# microcontroller_sch.net
KiCad netlist of a schematic drawn in Altium Designer
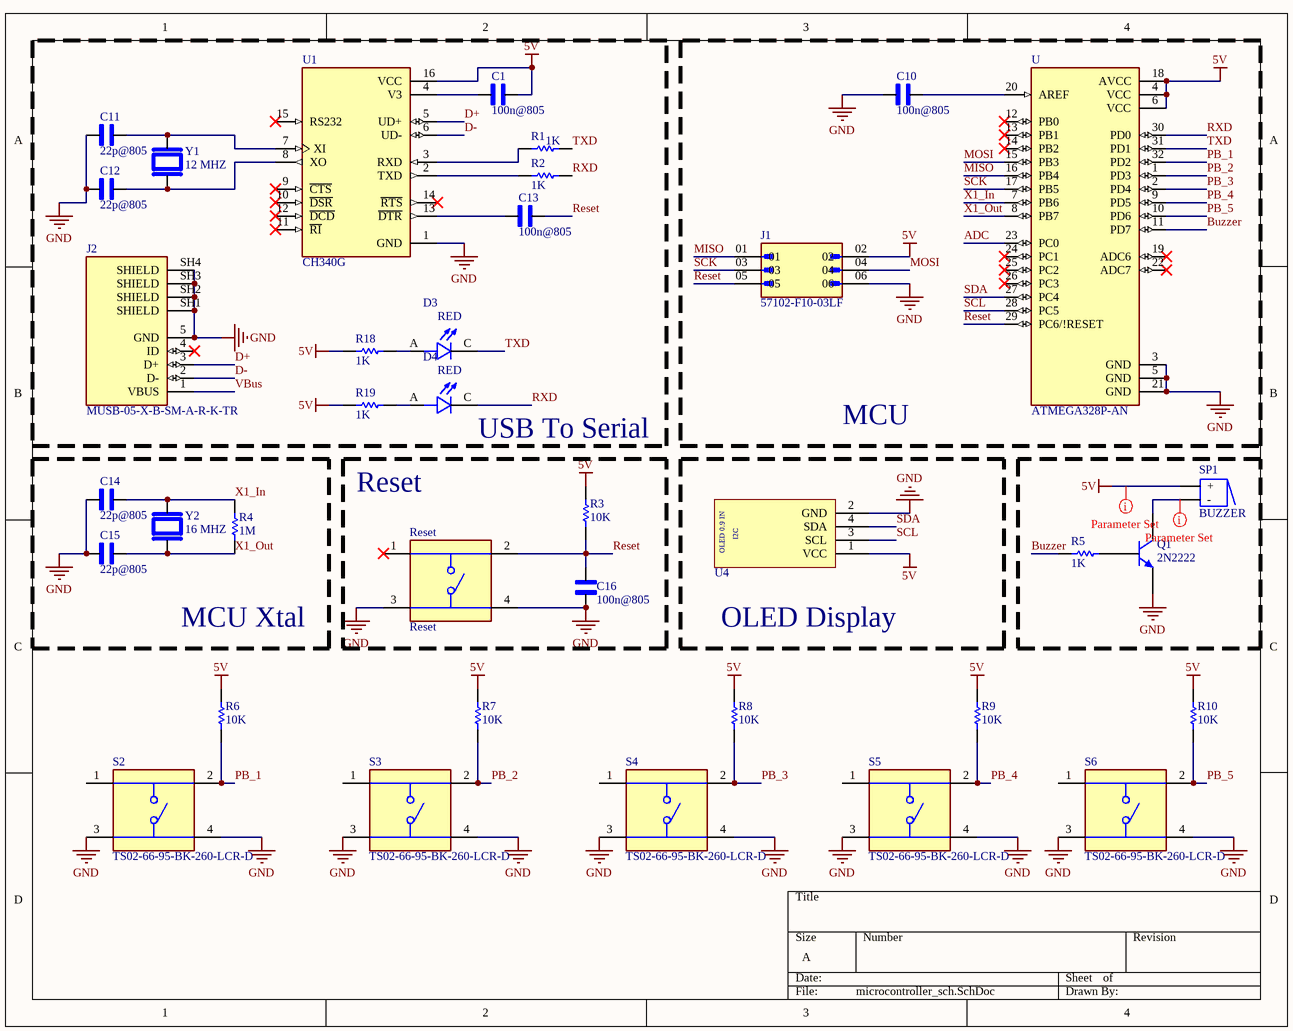
[diagram p0: microcontroller_sch.SchDoc]

(export (version "E")
  (design (tool "Eeschema 10.0.6"))
  (components
    (comp (ref "C1")
      (value "100n@805")
      (footprint "CAPC2012X95N")
      (description "Multilayer Ceramic Capacitors MLCC - SMD/SMT 50Vol 0.01uF X7R 805 10% AEC-Q200")
      (fields (field (name "MF") "YAGEO") (field (name "MP") "AC0805KPX7R9BB103"))
      (libsource (lib "AC0805KPX7R9BB103") (part "AC0805KPX7R9BB103"))
    )
    (comp (ref "C10")
      (value "100n@805")
      (footprint "CAPC2012X95N")
      (description "Multilayer Ceramic Capacitors MLCC - SMD/SMT 50Vol 0.01uF X7R 805 10% AEC-Q200")
      (fields (field (name "MF") "YAGEO") (field (name "MP") "AC0805KPX7R9BB103"))
      (libsource (lib "AC0805KPX7R9BB103") (part "AC0805KPX7R9BB103"))
    )
    (comp (ref "C11")
      (value "22p@805")
      (footprint "CAPC2012X95N")
      (description "Multilayer Ceramic Capacitors MLCC - SMD/SMT 50Vol 0.01uF X7R 805 10% AEC-Q200")
      (fields (field (name "MF") "YAGEO") (field (name "MP") "AC0805KPX7R9BB103"))
      (libsource (lib "AC0805KPX7R9BB103") (part "AC0805KPX7R9BB103"))
    )
    (comp (ref "C12")
      (value "22p@805")
      (footprint "CAPC2012X95N")
      (description "Multilayer Ceramic Capacitors MLCC - SMD/SMT 50Vol 0.01uF X7R 805 10% AEC-Q200")
      (fields (field (name "MF") "YAGEO") (field (name "MP") "AC0805KPX7R9BB103"))
      (libsource (lib "AC0805KPX7R9BB103") (part "AC0805KPX7R9BB103"))
    )
    (comp (ref "C13")
      (value "100n@805")
      (footprint "CAPC2012X95N")
      (description "Multilayer Ceramic Capacitors MLCC - SMD/SMT 50Vol 0.01uF X7R 805 10% AEC-Q200")
      (fields (field (name "MF") "YAGEO") (field (name "MP") "AC0805KPX7R9BB103"))
      (libsource (lib "AC0805KPX7R9BB103") (part "AC0805KPX7R9BB103"))
    )
    (comp (ref "C14")
      (value "22p@805")
      (footprint "CAPC2012X95N")
      (description "Multilayer Ceramic Capacitors MLCC - SMD/SMT 50Vol 0.01uF X7R 805 10% AEC-Q200")
      (fields (field (name "MF") "YAGEO") (field (name "MP") "AC0805KPX7R9BB103"))
      (libsource (lib "AC0805KPX7R9BB103") (part "AC0805KPX7R9BB103"))
    )
    (comp (ref "C15")
      (value "22p@805")
      (footprint "CAPC2012X95N")
      (description "Multilayer Ceramic Capacitors MLCC - SMD/SMT 50Vol 0.01uF X7R 805 10% AEC-Q200")
      (fields (field (name "MF") "YAGEO") (field (name "MP") "AC0805KPX7R9BB103"))
      (libsource (lib "AC0805KPX7R9BB103") (part "AC0805KPX7R9BB103"))
    )
    (comp (ref "C16")
      (value "100n@805")
      (footprint "CAPC2012X95N")
      (description "Multilayer Ceramic Capacitors MLCC - SMD/SMT 50Vol 0.01uF X7R 805 10% AEC-Q200")
      (fields (field (name "MF") "YAGEO") (field (name "MP") "AC0805KPX7R9BB103"))
      (libsource (lib "") (part "AC0805KPX7R9BB103_1"))
    )
    (comp (ref "D3")
      (value "7012X1")
      (footprint "LED_7012X1")
      (description "Red - LED Indication - Discrete 1.7V 0805 (2012 Metric)")
      (fields (field (name "MF") "VCC"))
      (libsource (lib "7012X1") (part "7012X1"))
    )
    (comp (ref "D4")
      (value "7012X1")
      (footprint "LED_7012X1")
      (description "Red - LED Indication - Discrete 1.7V 0805 (2012 Metric)")
      (fields (field (name "MF") "VCC"))
      (libsource (lib "7012X1") (part "7012X1"))
    )
    (comp (ref "J1")
      (value "57102-F10-03LF")
      (footprint "AMPHENOL_57102-F10-03LF")
      (description "Header, Through Hole, Double row, 6, 2mm (0.079in), Vertical")
      (fields (field (name "MF") "Amphenol ICC (FCI)"))
      (libsource (lib "57102-F10-03LF") (part "57102-F10-03LF"))
    )
    (comp (ref "J2")
      (value "MUSB-05-X-B-SM-A-R-K-TR")
      (footprint "SAMTEC_MUSB-05-X-B-SM-A-R-K-TR")
      (description "USB - mini B USB 2.0 Receptacle Connector 5 Position Surface Mount, Right Angle")
      (fields (field (name "MF") "Samtec") (field (name "MP") "MUSB-05-F-B-SM-A-R-K-TR"))
      (libsource (lib "MUSB-05-X-B-SM-A-R-K-TR") (part "MUSB-05-X-B-SM-A-R-K-TR"))
    )
    (comp (ref "Q1")
      (value "2N2222")
      (footprint "2n2222 TO92")
      (description "npn")
      (libsource (lib "2n2222") (part "2N2222"))
    )
    (comp (ref "R1")
      (value "1K")
      (footprint "RES0805")
      (description "RES0805")
      (libsource (lib "RES0805") (part "RES0805"))
    )
    (comp (ref "R2")
      (value "1K")
      (footprint "RES0805")
      (description "RES0805")
      (libsource (lib "RES0805") (part "RES0805"))
    )
    (comp (ref "R3")
      (value "10K")
      (footprint "RES0805")
      (description "RES0805")
      (libsource (lib "RES0805") (part "RES0805"))
    )
    (comp (ref "R4")
      (value "1M")
      (footprint "RES0805")
      (description "RES0805")
      (libsource (lib "RES0805") (part "RES0805"))
    )
    (comp (ref "R5")
      (value "1K")
      (footprint "RES0805")
      (description "RES0805")
      (libsource (lib "RES0805") (part "RES0805"))
    )
    (comp (ref "R6")
      (value "10K")
      (footprint "RES0805")
      (description "RES0805")
      (libsource (lib "RES0805") (part "RES0805"))
    )
    (comp (ref "R7")
      (value "10K")
      (footprint "RES0805")
      (description "RES0805")
      (libsource (lib "RES0805") (part "RES0805"))
    )
    (comp (ref "R8")
      (value "10K")
      (footprint "RES0805")
      (description "RES0805")
      (libsource (lib "RES0805") (part "RES0805"))
    )
    (comp (ref "R9")
      (value "10K")
      (footprint "RES0805")
      (description "RES0805")
      (libsource (lib "RES0805") (part "RES0805"))
    )
    (comp (ref "R10")
      (value "10K")
      (footprint "RES0805")
      (description "RES0805")
      (libsource (lib "RES0805") (part "RES0805"))
    )
    (comp (ref "R18")
      (value "1K")
      (footprint "RES0805")
      (description "RES0805")
      (libsource (lib "RES0805") (part "RES0805"))
    )
    (comp (ref "R19")
      (value "1K")
      (footprint "RES0805")
      (description "RES0805")
      (libsource (lib "RES0805") (part "RES0805"))
    )
    (comp (ref "Reset")
      (value "Reset")
      (footprint "SW_TS02-66-95-BK-260-LCR-D")
      (fields (field (name "MP") "TS02-66-95-BK-260-LCR-D"))
      (libsource (lib "TS02-66-95-BK-260-LCR-D") (part "TS02-66-95-BK-260-LCR-D"))
    )
    (comp (ref "S2")
      (value "TS02-66-95-BK-260-LCR-D")
      (footprint "SW_TS02-66-95-BK-260-LCR-D")
      (libsource (lib "TS02-66-95-BK-260-LCR-D") (part "TS02-66-95-BK-260-LCR-D"))
    )
    (comp (ref "S3")
      (value "TS02-66-95-BK-260-LCR-D")
      (footprint "SW_TS02-66-95-BK-260-LCR-D")
      (libsource (lib "TS02-66-95-BK-260-LCR-D") (part "TS02-66-95-BK-260-LCR-D"))
    )
    (comp (ref "S4")
      (value "TS02-66-95-BK-260-LCR-D")
      (footprint "SW_TS02-66-95-BK-260-LCR-D")
      (libsource (lib "TS02-66-95-BK-260-LCR-D") (part "TS02-66-95-BK-260-LCR-D"))
    )
    (comp (ref "S5")
      (value "TS02-66-95-BK-260-LCR-D")
      (footprint "SW_TS02-66-95-BK-260-LCR-D")
      (libsource (lib "TS02-66-95-BK-260-LCR-D") (part "TS02-66-95-BK-260-LCR-D"))
    )
    (comp (ref "S6")
      (value "TS02-66-95-BK-260-LCR-D")
      (footprint "SW_TS02-66-95-BK-260-LCR-D")
      (libsource (lib "TS02-66-95-BK-260-LCR-D") (part "TS02-66-95-BK-260-LCR-D"))
    )
    (comp (ref "SP1")
      (value "BUZZER")
      (footprint "BUZZER 7.62 mm DC")
      (libsource (lib "BUZZER") (part "BUZZER"))
    )
    (comp (ref "U")
      (value "ATMEGA328P-AN")
      (footprint "QFP80P900X900X120-32N")
      (description "AVR AVRÂ® ATmega Microcontroller IC 8-Bit 20MHz 32KB _16K x 16_ FLASH 32-TQFP _7x7_")
      (fields (field (name "MF") "Microchip"))
      (libsource (lib "ATMEGA328P-AN") (part "ATMEGA328P-AN"))
    )
    (comp (ref "U1")
      (value "CH340G")
      (footprint "SOIC127P600X180-16N")
      (description "USB Interface Integrated Circuit")
      (fields (field (name "MP") "Ch340G") (field (name "MF") "WCH"))
      (libsource (lib "CH340G") (part "CH340G"))
    )
    (comp (ref "U4")
      (value "OLED SSD1306 I2C")
      (footprint "OLED_SSD1306_64_I2C")
      (description "OLED, SSD1306, 0.96\", 128X64, BREAKOUT I2C")
      (libsource (lib "OLED SSD1306 12C") (part "OLED SSD1306 I2C"))
    )
    (comp (ref "Y1")
      (value "12 MHZ")
      (footprint "XTAL_HC49P488W46L1150T500H350")
      (description "HC/49US (AT49) MICROPROCESSOR CRYSTAL")
      (fields (field (name "MF") "Abracon LLC") (field (name "MP") "ABL-22.1184MHZ-B2"))
      (libsource (lib "ABL-22.1184MHZ-B2") (part "ABL-22.1184MHZ-B2"))
    )
    (comp (ref "Y2")
      (value "16 MHZ")
      (footprint "XTAL_HC49P488W46L1150T500H350")
      (description "HC/49US (AT49) MICROPROCESSOR CRYSTAL")
      (fields (field (name "MF") "Abracon LLC") (field (name "MP") "ABL-22.1184MHZ-B2"))
      (libsource (lib "ABL-22.1184MHZ-B2") (part "ABL-22.1184MHZ-B2"))
    )
  )
  (nets
    (net (code "1") (name "/ADC") (class "Default")
      (node (ref "U") (pin "23") (pinfunction "PC0_23") (pintype "bidirectional"))
    )
    (net (code "2") (name "/Buzzer") (class "Default")
      (node (ref "R5") (pin "2") (pinfunction "2_2") (pintype "passive"))
      (node (ref "U") (pin "11") (pinfunction "PD7_11") (pintype "bidirectional"))
    )
    (net (code "3") (name "/D+") (class "Default")
      (node (ref "J2") (pin "3") (pinfunction "D+_3") (pintype "bidirectional"))
      (node (ref "U1") (pin "5") (pinfunction "UD+_5") (pintype "bidirectional"))
    )
    (net (code "4") (name "/D-") (class "Default")
      (node (ref "J2") (pin "2") (pinfunction "D-_2") (pintype "bidirectional"))
      (node (ref "U1") (pin "6") (pinfunction "UD-_6") (pintype "bidirectional"))
    )
    (net (code "5") (name "/MISO") (class "Default")
      (node (ref "J1") (pin "01") (pinfunction "01_01") (pintype "passive"))
      (node (ref "U") (pin "16") (pinfunction "PB4_16") (pintype "bidirectional"))
    )
    (net (code "6") (name "/MOSI") (class "Default")
      (node (ref "J1") (pin "04") (pinfunction "04_04") (pintype "passive"))
      (node (ref "U") (pin "15") (pinfunction "PB3_15") (pintype "bidirectional"))
    )
    (net (code "7") (name "/PB_1") (class "Default")
      (node (ref "R6") (pin "1") (pinfunction "1_1") (pintype "passive"))
      (node (ref "S2") (pin "2") (pinfunction "2_2") (pintype "passive"))
      (node (ref "U") (pin "32") (pinfunction "PD2_32") (pintype "bidirectional"))
    )
    (net (code "8") (name "/PB_2") (class "Default")
      (node (ref "R7") (pin "1") (pinfunction "1_1") (pintype "passive"))
      (node (ref "S3") (pin "2") (pinfunction "2_2") (pintype "passive"))
      (node (ref "U") (pin "1") (pinfunction "PD3_1") (pintype "bidirectional"))
    )
    (net (code "9") (name "/PB_3") (class "Default")
      (node (ref "R8") (pin "1") (pinfunction "1_1") (pintype "passive"))
      (node (ref "S4") (pin "2") (pinfunction "2_2") (pintype "passive"))
      (node (ref "U") (pin "2") (pinfunction "PD4_2") (pintype "bidirectional"))
    )
    (net (code "10") (name "/PB_4") (class "Default")
      (node (ref "R9") (pin "1") (pinfunction "1_1") (pintype "passive"))
      (node (ref "S5") (pin "2") (pinfunction "2_2") (pintype "passive"))
      (node (ref "U") (pin "9") (pinfunction "PD5_9") (pintype "bidirectional"))
    )
    (net (code "11") (name "/PB_5") (class "Default")
      (node (ref "R10") (pin "1") (pinfunction "1_1") (pintype "passive"))
      (node (ref "S6") (pin "2") (pinfunction "2_2") (pintype "passive"))
      (node (ref "U") (pin "10") (pinfunction "PD6_10") (pintype "bidirectional"))
    )
    (net (code "12") (name "/RXD") (class "Default")
      (node (ref "D4") (pin "C") (pinfunction "C_C") (pintype "passive"))
      (node (ref "R2") (pin "1") (pinfunction "1_1") (pintype "passive"))
      (node (ref "U") (pin "30") (pinfunction "PD0_30") (pintype "bidirectional"))
    )
    (net (code "13") (name "/Reset") (class "Default")
      (node (ref "C13") (pin "2") (pinfunction "2_2") (pintype "passive"))
      (node (ref "C16") (pin "2") (pinfunction "2_2") (pintype "passive"))
      (node (ref "J1") (pin "05") (pinfunction "05_05") (pintype "passive"))
      (node (ref "R3") (pin "1") (pinfunction "1_1") (pintype "passive"))
      (node (ref "Reset") (pin "2") (pinfunction "2_2") (pintype "passive"))
      (node (ref "U") (pin "29") (pinfunction "PC6/!RESET_29") (pintype "bidirectional"))
    )
    (net (code "14") (name "/SCK") (class "Default")
      (node (ref "J1") (pin "03") (pinfunction "03_03") (pintype "passive"))
      (node (ref "U") (pin "17") (pinfunction "PB5_17") (pintype "bidirectional"))
    )
    (net (code "15") (name "/SCL") (class "Default")
      (node (ref "U") (pin "28") (pinfunction "PC5_28") (pintype "bidirectional"))
      (node (ref "U4") (pin "3") (pinfunction "SCL_3") (pintype "passive"))
    )
    (net (code "16") (name "/SDA") (class "Default")
      (node (ref "U") (pin "27") (pinfunction "PC4_27") (pintype "bidirectional"))
      (node (ref "U4") (pin "4") (pinfunction "SDA_4") (pintype "passive"))
    )
    (net (code "17") (name "/TXD") (class "Default")
      (node (ref "D3") (pin "C") (pinfunction "C_C") (pintype "passive"))
      (node (ref "R1") (pin "1") (pinfunction "1_1") (pintype "passive"))
      (node (ref "U") (pin "31") (pinfunction "PD1_31") (pintype "bidirectional"))
    )
    (net (code "18") (name "/VBus") (class "Default")
      (node (ref "J2") (pin "1") (pinfunction "VBUS_1") (pintype "power_in"))
    )
    (net (code "19") (name "/X1_In") (class "Default")
      (node (ref "C14") (pin "2") (pinfunction "2_2") (pintype "passive"))
      (node (ref "R4") (pin "2") (pinfunction "2_2") (pintype "passive"))
      (node (ref "U") (pin "7") (pinfunction "PB6_7") (pintype "bidirectional"))
      (node (ref "Y2") (pin "1") (pinfunction "1_1") (pintype "passive"))
    )
    (net (code "20") (name "/X1_Out") (class "Default")
      (node (ref "C15") (pin "2") (pinfunction "2_2") (pintype "passive"))
      (node (ref "R4") (pin "1") (pinfunction "1_1") (pintype "passive"))
      (node (ref "U") (pin "8") (pinfunction "PB7_8") (pintype "bidirectional"))
      (node (ref "Y2") (pin "2") (pinfunction "2_2") (pintype "passive"))
    )
    (net (code "21") (name "5V") (class "Default")
      (node (ref "C1") (pin "2") (pinfunction "2_2") (pintype "passive"))
      (node (ref "J1") (pin "02") (pinfunction "02_02") (pintype "passive"))
      (node (ref "R10") (pin "2") (pinfunction "2_2") (pintype "passive"))
      (node (ref "R18") (pin "2") (pinfunction "2_2") (pintype "passive"))
      (node (ref "R19") (pin "2") (pinfunction "2_2") (pintype "passive"))
      (node (ref "R3") (pin "2") (pinfunction "2_2") (pintype "passive"))
      (node (ref "R6") (pin "2") (pinfunction "2_2") (pintype "passive"))
      (node (ref "R7") (pin "2") (pinfunction "2_2") (pintype "passive"))
      (node (ref "R8") (pin "2") (pinfunction "2_2") (pintype "passive"))
      (node (ref "R9") (pin "2") (pinfunction "2_2") (pintype "passive"))
      (node (ref "SP1") (pin "1") (pinfunction "+_1") (pintype "passive"))
      (node (ref "U") (pin "18") (pinfunction "AVCC_18") (pintype "power_in"))
      (node (ref "U") (pin "4") (pinfunction "VCC_4") (pintype "power_in"))
      (node (ref "U") (pin "6") (pinfunction "VCC_6") (pintype "power_in"))
      (node (ref "U1") (pin "16") (pinfunction "VCC_16") (pintype "power_in"))
      (node (ref "U4") (pin "1") (pinfunction "VCC_1") (pintype "passive"))
    )
    (net (code "22") (name "GND") (class "Default")
      (node (ref "C10") (pin "1") (pinfunction "1_1") (pintype "passive"))
      (node (ref "C11") (pin "1") (pinfunction "1_1") (pintype "passive"))
      (node (ref "C12") (pin "1") (pinfunction "1_1") (pintype "passive"))
      (node (ref "C14") (pin "1") (pinfunction "1_1") (pintype "passive"))
      (node (ref "C15") (pin "1") (pinfunction "1_1") (pintype "passive"))
      (node (ref "C16") (pin "1") (pinfunction "1_1") (pintype "passive"))
      (node (ref "J1") (pin "06") (pinfunction "06_06") (pintype "passive"))
      (node (ref "J2") (pin "5") (pinfunction "GND_5") (pintype "power_in"))
      (node (ref "J2") (pin "SH1") (pinfunction "SHIELD_SH1") (pintype "passive"))
      (node (ref "J2") (pin "SH2") (pinfunction "SHIELD_SH2") (pintype "passive"))
      (node (ref "J2") (pin "SH3") (pinfunction "SHIELD_SH3") (pintype "passive"))
      (node (ref "J2") (pin "SH4") (pinfunction "SHIELD_SH4") (pintype "passive"))
      (node (ref "Q1") (pin "3") (pinfunction "E_3") (pintype "passive"))
      (node (ref "Reset") (pin "3") (pinfunction "3_3") (pintype "passive"))
      (node (ref "Reset") (pin "4") (pinfunction "4_4") (pintype "passive"))
      (node (ref "S2") (pin "3") (pinfunction "3_3") (pintype "passive"))
      (node (ref "S2") (pin "4") (pinfunction "4_4") (pintype "passive"))
      (node (ref "S3") (pin "3") (pinfunction "3_3") (pintype "passive"))
      (node (ref "S3") (pin "4") (pinfunction "4_4") (pintype "passive"))
      (node (ref "S4") (pin "3") (pinfunction "3_3") (pintype "passive"))
      (node (ref "S4") (pin "4") (pinfunction "4_4") (pintype "passive"))
      (node (ref "S5") (pin "3") (pinfunction "3_3") (pintype "passive"))
      (node (ref "S5") (pin "4") (pinfunction "4_4") (pintype "passive"))
      (node (ref "S6") (pin "3") (pinfunction "3_3") (pintype "passive"))
      (node (ref "S6") (pin "4") (pinfunction "4_4") (pintype "passive"))
      (node (ref "U") (pin "21") (pinfunction "GND_21") (pintype "power_in"))
      (node (ref "U") (pin "3") (pinfunction "GND_3") (pintype "power_in"))
      (node (ref "U") (pin "5") (pinfunction "GND_5") (pintype "power_in"))
      (node (ref "U1") (pin "1") (pinfunction "GND_1") (pintype "power_in"))
      (node (ref "U4") (pin "2") (pinfunction "GND_2") (pintype "passive"))
    )
    (net (code "23") (name "Net-(D3-PadA)") (class "Default")
      (node (ref "D3") (pin "A") (pinfunction "A_A") (pintype "passive"))
      (node (ref "R18") (pin "1") (pinfunction "1_1") (pintype "passive"))
    )
    (net (code "24") (name "Net-(D4-PadA)") (class "Default")
      (node (ref "D4") (pin "A") (pinfunction "A_A") (pintype "passive"))
      (node (ref "R19") (pin "1") (pinfunction "1_1") (pintype "passive"))
    )
    (net (code "25") (name "Net-(Q1-B)") (class "Default")
      (node (ref "Q1") (pin "1") (pinfunction "B_1") (pintype "passive"))
      (node (ref "R5") (pin "1") (pinfunction "1_1") (pintype "passive"))
    )
    (net (code "26") (name "Net-(Q1-C)") (class "Default")
      (node (ref "Q1") (pin "2") (pinfunction "C_2") (pintype "passive"))
      (node (ref "SP1") (pin "2") (pinfunction "-_2") (pintype "passive"))
    )
    (net (code "27") (name "Net-(U-AREF)") (class "Default")
      (node (ref "C10") (pin "2") (pinfunction "2_2") (pintype "passive"))
      (node (ref "U") (pin "20") (pinfunction "AREF_20") (pintype "input"))
    )
    (net (code "28") (name "Net-(U1-RXD)") (class "Default")
      (node (ref "R1") (pin "2") (pinfunction "2_2") (pintype "passive"))
      (node (ref "U1") (pin "3") (pinfunction "RXD_3") (pintype "input"))
    )
    (net (code "29") (name "Net-(U1-TXD)") (class "Default")
      (node (ref "R2") (pin "2") (pinfunction "2_2") (pintype "passive"))
      (node (ref "U1") (pin "2") (pinfunction "TXD_2") (pintype "output"))
    )
    (net (code "30") (name "Net-(U1-V3)") (class "Default")
      (node (ref "C1") (pin "1") (pinfunction "1_1") (pintype "passive"))
      (node (ref "U1") (pin "4") (pinfunction "V3_4") (pintype "power_in"))
    )
    (net (code "31") (name "Net-(U1-XI)") (class "Default")
      (node (ref "C11") (pin "2") (pinfunction "2_2") (pintype "passive"))
      (node (ref "U1") (pin "7") (pinfunction "XI_7") (pintype "input"))
      (node (ref "Y1") (pin "1") (pinfunction "1_1") (pintype "passive"))
    )
    (net (code "32") (name "Net-(U1-XO)") (class "Default")
      (node (ref "C12") (pin "2") (pinfunction "2_2") (pintype "passive"))
      (node (ref "U1") (pin "8") (pinfunction "XO_8") (pintype "output"))
      (node (ref "Y1") (pin "2") (pinfunction "2_2") (pintype "passive"))
    )
    (net (code "33") (name "Net-(U1-~{DTR})") (class "Default")
      (node (ref "C13") (pin "1") (pinfunction "1_1") (pintype "passive"))
      (node (ref "U1") (pin "13") (pinfunction "~{DTR}_13") (pintype "output"))
    )
    (net (code "34") (name "unconnected-(J2-ID-Pad4)") (class "Default")
      (node (ref "J2") (pin "4") (pinfunction "ID_4") (pintype "bidirectional+no_connect"))
    )
    (net (code "35") (name "unconnected-(Reset-Pad1)") (class "Default")
      (node (ref "Reset") (pin "1") (pinfunction "1_1") (pintype "passive+no_connect"))
    )
    (net (code "36") (name "unconnected-(S2-Pad1)") (class "Default")
      (node (ref "S2") (pin "1") (pinfunction "1_1") (pintype "passive"))
    )
    (net (code "37") (name "unconnected-(S3-Pad1)") (class "Default")
      (node (ref "S3") (pin "1") (pinfunction "1_1") (pintype "passive"))
    )
    (net (code "38") (name "unconnected-(S4-Pad1)") (class "Default")
      (node (ref "S4") (pin "1") (pinfunction "1_1") (pintype "passive"))
    )
    (net (code "39") (name "unconnected-(S5-Pad1)") (class "Default")
      (node (ref "S5") (pin "1") (pinfunction "1_1") (pintype "passive"))
    )
    (net (code "40") (name "unconnected-(S6-Pad1)") (class "Default")
      (node (ref "S6") (pin "1") (pinfunction "1_1") (pintype "passive"))
    )
    (net (code "41") (name "unconnected-(U-ADC6-Pad19)") (class "Default")
      (node (ref "U") (pin "19") (pinfunction "ADC6_19") (pintype "bidirectional+no_connect"))
    )
    (net (code "42") (name "unconnected-(U-ADC7-Pad22)") (class "Default")
      (node (ref "U") (pin "22") (pinfunction "ADC7_22") (pintype "bidirectional+no_connect"))
    )
    (net (code "43") (name "unconnected-(U-PB0-Pad12)") (class "Default")
      (node (ref "U") (pin "12") (pinfunction "PB0_12") (pintype "bidirectional+no_connect"))
    )
    (net (code "44") (name "unconnected-(U-PB1-Pad13)") (class "Default")
      (node (ref "U") (pin "13") (pinfunction "PB1_13") (pintype "bidirectional+no_connect"))
    )
    (net (code "45") (name "unconnected-(U-PB2-Pad14)") (class "Default")
      (node (ref "U") (pin "14") (pinfunction "PB2_14") (pintype "bidirectional+no_connect"))
    )
    (net (code "46") (name "unconnected-(U-PC1-Pad24)") (class "Default")
      (node (ref "U") (pin "24") (pinfunction "PC1_24") (pintype "bidirectional+no_connect"))
    )
    (net (code "47") (name "unconnected-(U-PC2-Pad25)") (class "Default")
      (node (ref "U") (pin "25") (pinfunction "PC2_25") (pintype "bidirectional+no_connect"))
    )
    (net (code "48") (name "unconnected-(U-PC3-Pad26)") (class "Default")
      (node (ref "U") (pin "26") (pinfunction "PC3_26") (pintype "bidirectional+no_connect"))
    )
    (net (code "49") (name "unconnected-(U1-RS232-Pad15)") (class "Default")
      (node (ref "U1") (pin "15") (pinfunction "RS232_15") (pintype "input+no_connect"))
    )
    (net (code "50") (name "unconnected-(U1-~{CTS}-Pad9)") (class "Default")
      (node (ref "U1") (pin "9") (pinfunction "~{CTS}_9") (pintype "input+no_connect"))
    )
    (net (code "51") (name "unconnected-(U1-~{DCD}-Pad12)") (class "Default")
      (node (ref "U1") (pin "12") (pinfunction "~{DCD}_12") (pintype "input+no_connect"))
    )
    (net (code "52") (name "unconnected-(U1-~{DSR}-Pad10)") (class "Default")
      (node (ref "U1") (pin "10") (pinfunction "~{DSR}_10") (pintype "input+no_connect"))
    )
    (net (code "53") (name "unconnected-(U1-~{RI}-Pad11)") (class "Default")
      (node (ref "U1") (pin "11") (pinfunction "~{RI}_11") (pintype "input+no_connect"))
    )
    (net (code "54") (name "unconnected-(U1-~{RTS}-Pad14)") (class "Default")
      (node (ref "U1") (pin "14") (pinfunction "~{RTS}_14") (pintype "output+no_connect"))
    )
  )
)
